# PSU.net
KiCad netlist of a schematic drawn in Altium Designer
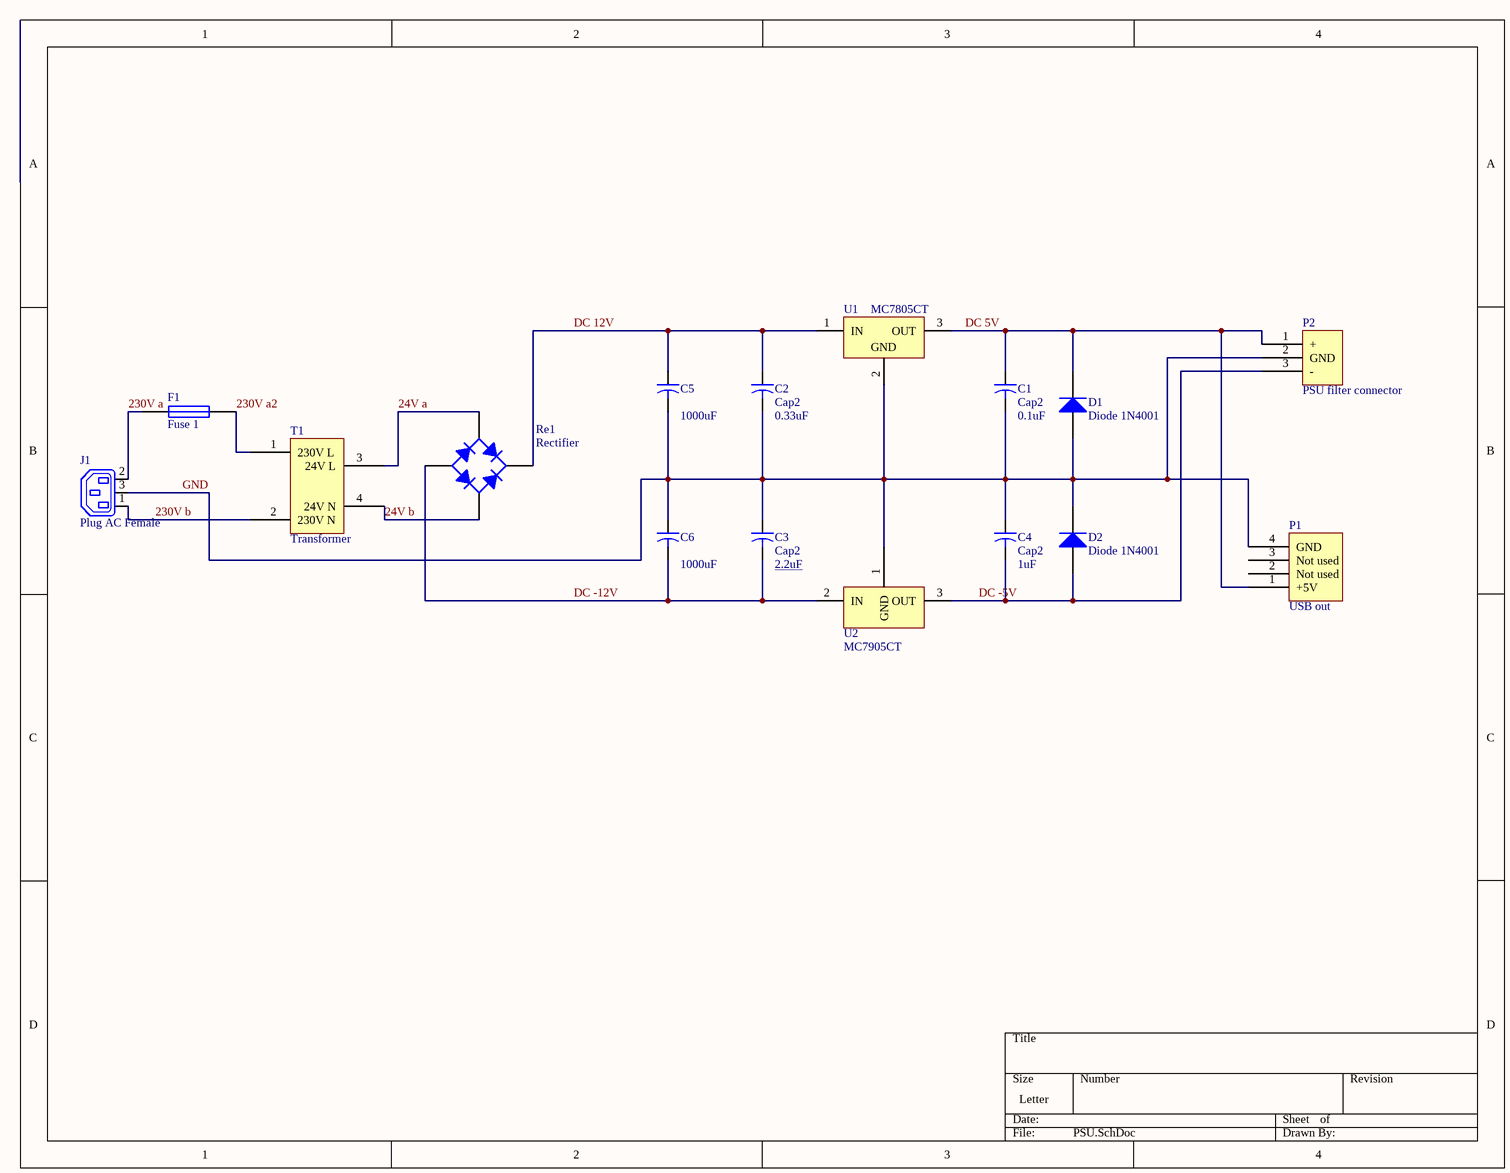
[diagram p0: PSU.SchDoc]

(export (version "E")
  (design (tool "Eeschema 10.0.6"))
  (components
    (comp (ref "C1")
      (value "Cap2")
      (footprint "Cap Jamicon 1uF")
      (description "Capacitor")
      (fields (field (name "ALTIUM_VALUE") "0.1uF") (field (name "PUBLISHER") "Altium Limited"))
      (libsource (lib "Miscellaneous Devices") (part "Cap2"))
    )
    (comp (ref "C2")
      (value "Cap2")
      (footprint "Cap Jamicon 330nF")
      (description "Capacitor")
      (fields (field (name "ALTIUM_VALUE") "0.33uF") (field (name "PUBLISHER") "Altium Limited"))
      (libsource (lib "Miscellaneous Devices") (part "Cap2"))
    )
    (comp (ref "C3")
      (value "Cap2")
      (footprint "Cap Panasonic 2.2uF")
      (description "Capacitor")
      (fields (field (name "ALTIUM_VALUE") "2.2uF") (field (name "PUBLISHER") "Altium Limited"))
      (libsource (lib "Miscellaneous Devices") (part "Cap2"))
    )
    (comp (ref "C4")
      (value "Cap2")
      (footprint "Cap Jamicon 1uF")
      (description "Capacitor")
      (fields (field (name "ALTIUM_VALUE") "1uF") (field (name "PUBLISHER") "Altium Limited"))
      (libsource (lib "Miscellaneous Devices") (part "Cap2"))
    )
    (comp (ref "C5")
      (value "1000uF")
      (footprint "Cap 1000uF")
      (description "Cap")
      (fields (field (name "PUBLISHER") "Altium Limited"))
      (libsource (lib "PSU") (part "Cap2"))
    )
    (comp (ref "C6")
      (value "1000uF")
      (footprint "Cap 1000uF")
      (description "Cap")
      (fields (field (name "PUBLISHER") "Altium Limited"))
      (libsource (lib "PSU") (part "Cap2"))
    )
    (comp (ref "D1")
      (value "Diode 1N4001")
      (footprint "DO-41")
      (description "1 Amp General Purpose Rectifier")
      (fields (field (name "PUBLISHER") "Altium Limited"))
      (libsource (lib "Miscellaneous Devices") (part "Diode 1N4001"))
    )
    (comp (ref "D2")
      (value "Diode 1N4001")
      (footprint "DO-41")
      (description "1 Amp General Purpose Rectifier")
      (fields (field (name "PUBLISHER") "Altium Limited"))
      (libsource (lib "Miscellaneous Devices") (part "Diode 1N4001"))
    )
    (comp (ref "F1")
      (value "Fuse 1")
      (footprint "Fuse 22mm")
      (description "Fuse")
      (fields (field (name "PUBLISHER") "Altium Limited"))
      (libsource (lib "Miscellaneous Devices") (part "Fuse 1"))
    )
    (comp (ref "J1")
      (value "Plug AC Female")
      (footprint "Power input PSU")
      (description "IEC Mains Power Outlet, EN60 320-2-2 F Class I, PC Flange Rear Mount, Chassis Socket")
      (fields (field (name "PUBLISHER") "Altium Limited"))
      (libsource (lib "Miscellaneous Connectors") (part "Plug AC Female"))
    )
    (comp (ref "P1") (value "USB out") (footprint "USB out") (libsource (lib "PSU") (part "USB out")))
    (comp (ref "P2")
      (value "PSU filter connector")
      (footprint "PSU filter connector")
      (libsource (lib "PSU") (part "PSU filter connector"))
    )
    (comp (ref "Re1")
      (value "Rectifier")
      (footprint "Rectifier PSU")
      (description "Full Wave Diode Bridge")
      (fields (field (name "PUBLISHER") "Altium Limited"))
      (libsource (lib "PSU") (part "Bridge1 Resonator PSU"))
    )
    (comp (ref "T1")
      (value "Transformer")
      (footprint "Transformator")
      (libsource (lib "PSU") (part "Transformer"))
    )
    (comp (ref "U1")
      (value "MC7805CT")
      (footprint "221A-06")
      (description "Three-Terminal Positive Voltage Regulator")
      (fields (field (name "PUBLISHER") "Altium Limited"))
      (libsource (lib "ON Semi Power Mgt Voltage Regulator") (part "MC7805CT"))
    )
    (comp (ref "U2")
      (value "MC7905CT")
      (footprint "221A-09")
      (description "Three-Terminal Negative Voltage Regulator")
      (fields (field (name "PUBLISHER") "Altium Limited"))
      (libsource (lib "PSU") (part "MC7905CT"))
    )
  )
  (nets
    (net (code "1") (name "/24V a") (class "Default")
      (node (ref "Re1") (pin "4") (pinfunction "C_4") (pintype "passive"))
      (node (ref "T1") (pin "3") (pinfunction "24V_L_3") (pintype "passive"))
    )
    (net (code "2") (name "/24V b") (class "Default")
      (node (ref "Re1") (pin "2") (pinfunction "C_2") (pintype "passive"))
      (node (ref "T1") (pin "4") (pinfunction "24V_N_4") (pintype "passive"))
    )
    (net (code "3") (name "/230V a") (class "Default")
      (node (ref "F1") (pin "1") (pinfunction "1_1") (pintype "passive"))
      (node (ref "J1") (pin "2") (pinfunction "N_2") (pintype "power_in"))
    )
    (net (code "4") (name "/230V a2") (class "Default")
      (node (ref "F1") (pin "2") (pinfunction "2_2") (pintype "passive"))
      (node (ref "T1") (pin "1") (pinfunction "230V_L_1") (pintype "passive"))
    )
    (net (code "5") (name "/230V b") (class "Default")
      (node (ref "J1") (pin "1") (pinfunction "L_1") (pintype "power_in"))
      (node (ref "T1") (pin "2") (pinfunction "230V_N_2") (pintype "passive"))
    )
    (net (code "6") (name "/DC -5V") (class "Default")
      (node (ref "C4") (pin "2") (pinfunction "2_2") (pintype "passive"))
      (node (ref "D2") (pin "1") (pinfunction "A_1") (pintype "passive"))
      (node (ref "P2") (pin "3") (pinfunction "-_3") (pintype "passive"))
      (node (ref "U2") (pin "3") (pinfunction "OUT_3") (pintype "power_in"))
    )
    (net (code "7") (name "/DC -12V") (class "Default")
      (node (ref "C3") (pin "2") (pinfunction "2_2") (pintype "passive"))
      (node (ref "C6") (pin "2") (pinfunction "2_2") (pintype "passive"))
      (node (ref "Re1") (pin "3") (pinfunction "A_3") (pintype "passive"))
      (node (ref "U2") (pin "2") (pinfunction "IN_2") (pintype "power_in"))
    )
    (net (code "8") (name "/DC 5V") (class "Default")
      (node (ref "C1") (pin "1") (pinfunction "1_1") (pintype "passive"))
      (node (ref "D1") (pin "2") (pinfunction "K_2") (pintype "passive"))
      (node (ref "P1") (pin "1") (pinfunction "+5V_1") (pintype "passive"))
      (node (ref "P2") (pin "1") (pinfunction "+_1") (pintype "passive"))
      (node (ref "U1") (pin "3") (pinfunction "OUT_3") (pintype "power_in"))
    )
    (net (code "9") (name "/DC 12V") (class "Default")
      (node (ref "C2") (pin "1") (pinfunction "1_1") (pintype "passive"))
      (node (ref "C5") (pin "1") (pinfunction "1_1") (pintype "passive"))
      (node (ref "Re1") (pin "1") (pinfunction "K_1") (pintype "passive"))
      (node (ref "U1") (pin "1") (pinfunction "IN_1") (pintype "power_in"))
    )
    (net (code "10") (name "/GND") (class "Default")
      (node (ref "C1") (pin "2") (pinfunction "2_2") (pintype "passive"))
      (node (ref "C2") (pin "2") (pinfunction "2_2") (pintype "passive"))
      (node (ref "C3") (pin "1") (pinfunction "1_1") (pintype "passive"))
      (node (ref "C4") (pin "1") (pinfunction "1_1") (pintype "passive"))
      (node (ref "C5") (pin "2") (pinfunction "2_2") (pintype "passive"))
      (node (ref "C6") (pin "1") (pinfunction "1_1") (pintype "passive"))
      (node (ref "D1") (pin "1") (pinfunction "A_1") (pintype "passive"))
      (node (ref "D2") (pin "2") (pinfunction "K_2") (pintype "passive"))
      (node (ref "J1") (pin "3") (pinfunction "E_3") (pintype "power_in"))
      (node (ref "P1") (pin "4") (pinfunction "GND_4") (pintype "passive"))
      (node (ref "P2") (pin "2") (pinfunction "GND_2") (pintype "passive"))
      (node (ref "U1") (pin "2") (pinfunction "GND_2") (pintype "power_in"))
      (node (ref "U2") (pin "1") (pinfunction "GND_1") (pintype "passive"))
    )
    (net (code "11") (name "unconnected-(P1-Not_used-Pad2)") (class "Default")
      (node (ref "P1") (pin "2") (pinfunction "Not_used_2") (pintype "passive"))
    )
    (net (code "12") (name "unconnected-(P1-Not_used-Pad3)") (class "Default")
      (node (ref "P1") (pin "3") (pinfunction "Not_used_3") (pintype "passive"))
    )
  )
)
